# diy_stm.net
KiCad netlist of a schematic drawn in Altium Designer
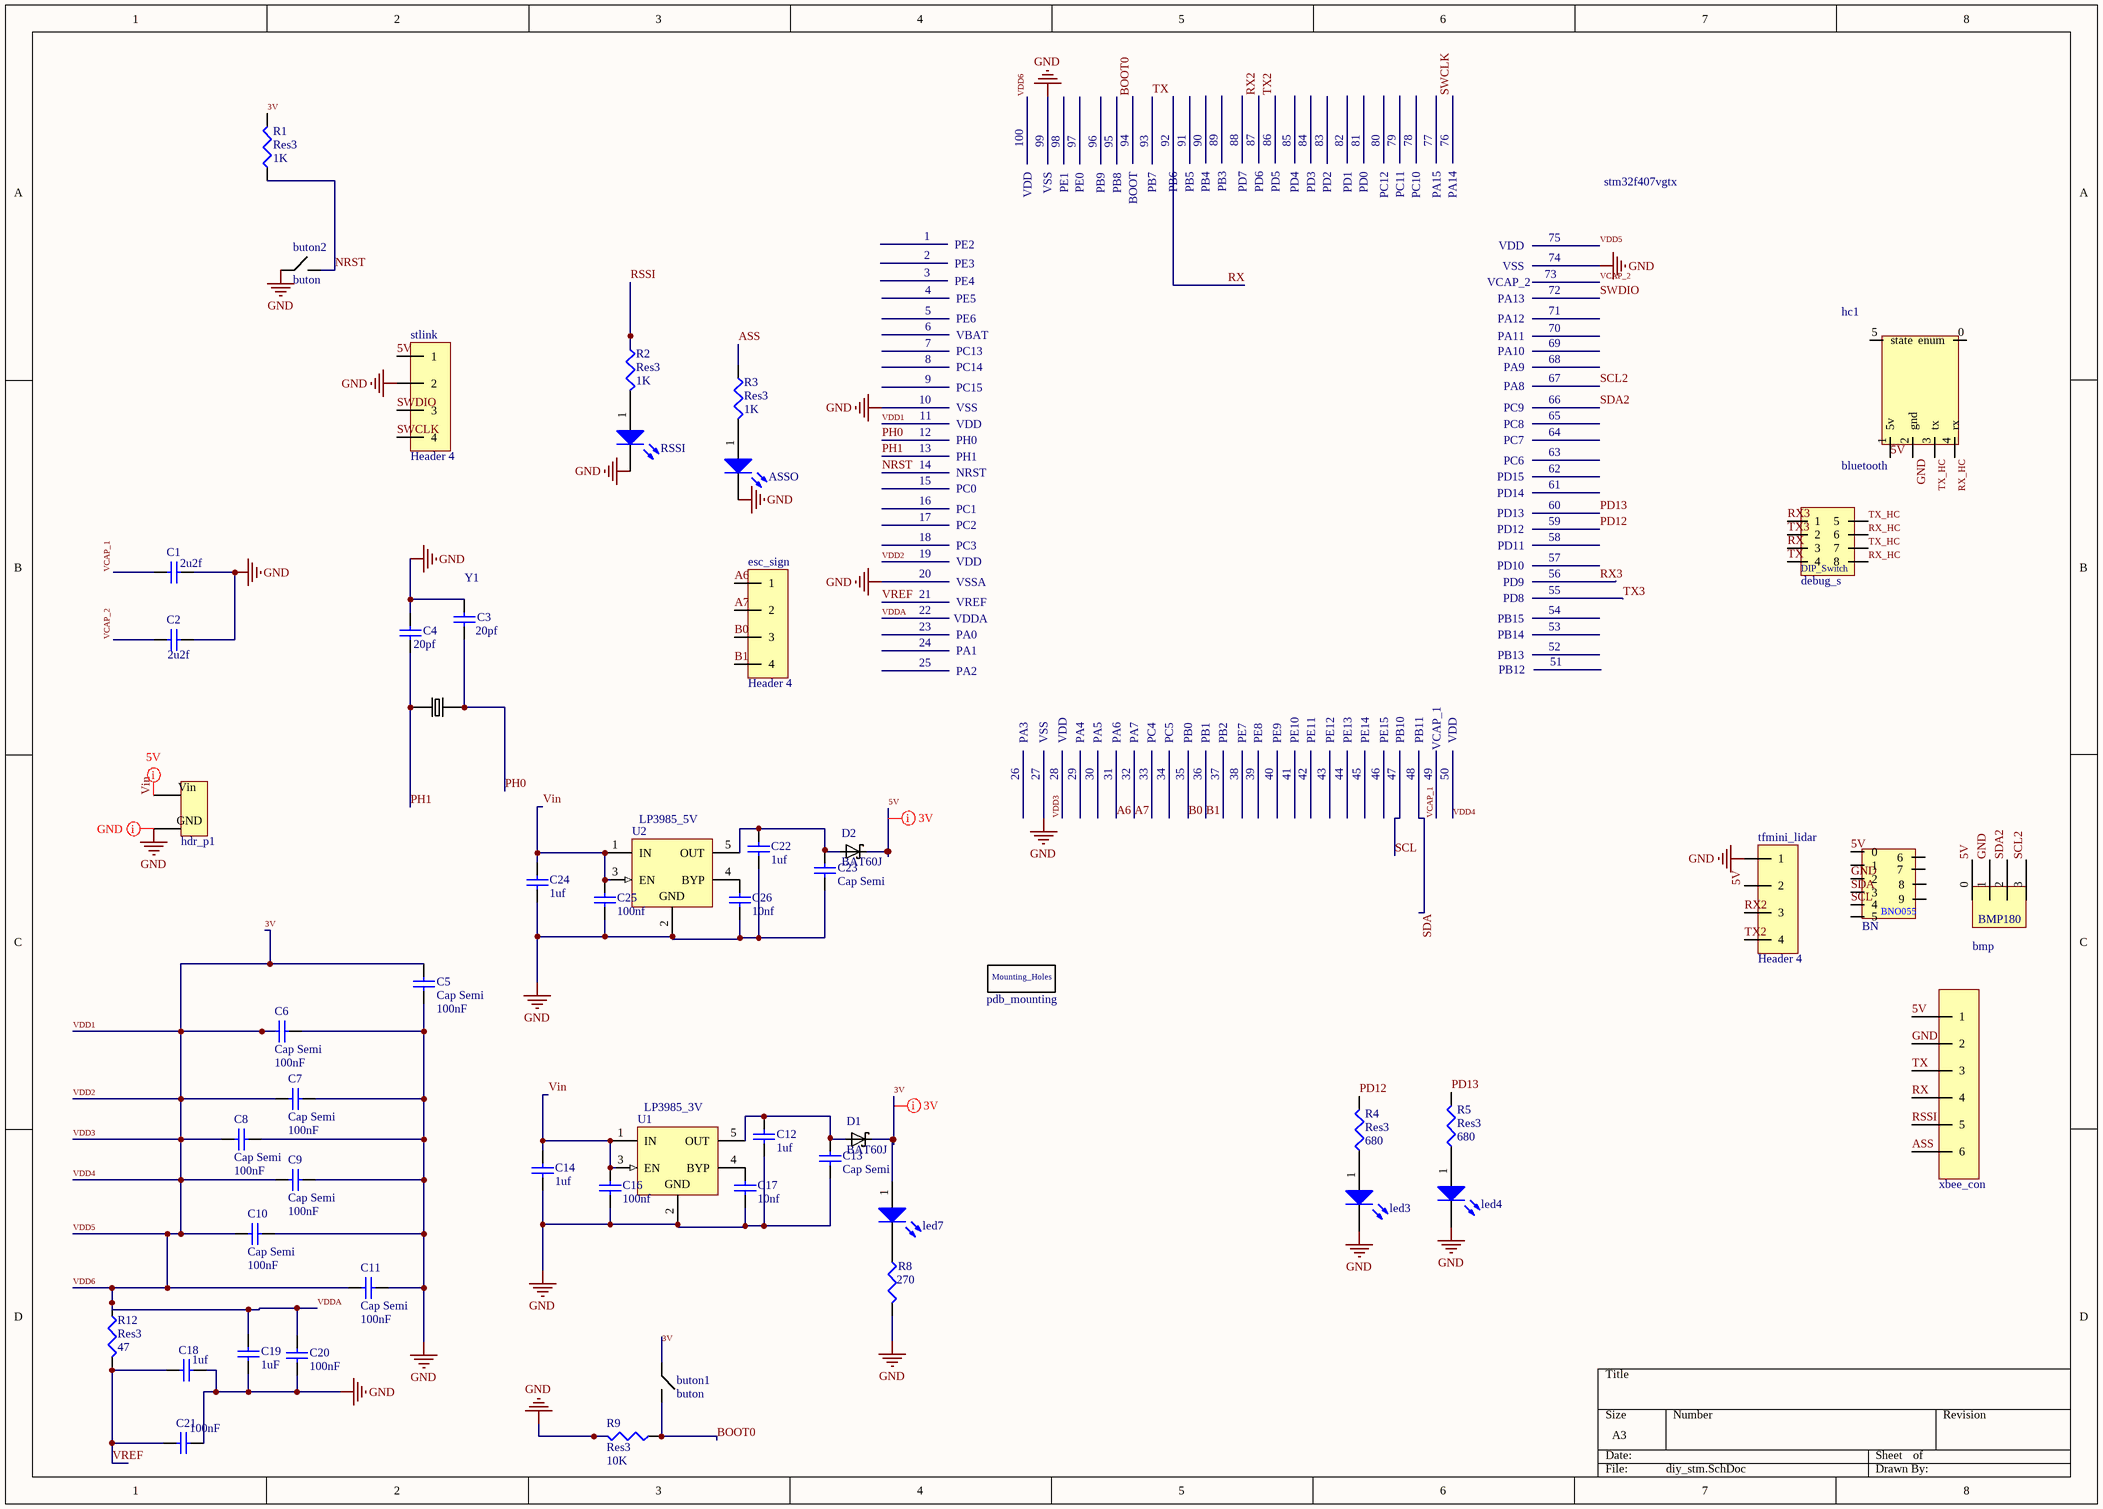
[diagram p0: diy_stm.SchDoc]

(export (version "E")
  (design (tool "Eeschema 10.0.6"))
  (components
    (comp (ref "ASSO")
      (value "L_green")
      (footprint "LED_0603")
      (libsource (lib "Led_edited") (part "L_green"))
    )
    (comp (ref "bmp") (value "bmp") (footprint "bmp") (libsource (lib "bmp180") (part "bmp")))
    (comp (ref "BN") (value "BNO055") (footprint "bno055") (libsource (lib "bno055") (part "BNO055")))
    (comp (ref "buton1") (value "buton") (footprint "buton") (libsource (lib "resistance") (part "buton")))
    (comp (ref "buton2") (value "buton") (footprint "buton") (libsource (lib "resistance") (part "buton")))
    (comp (ref "C1")
      (value "2u2f")
      (footprint "0603")
      (description "Capacitor (Semiconductor SIM Model)")
      (fields (field (name "Comment") "Cap Semi") (field (name "PUBLISHER") "Altium Limited"))
      (libsource (lib "Miscellaneous Devices") (part "Cap Semi"))
    )
    (comp (ref "C2")
      (value "2u2f")
      (footprint "0603")
      (description "Capacitor (Semiconductor SIM Model)")
      (fields (field (name "Comment") "Cap Semi") (field (name "PUBLISHER") "Altium Limited"))
      (libsource (lib "Miscellaneous Devices") (part "Cap Semi"))
    )
    (comp (ref "C3")
      (value "20pf")
      (footprint "0603")
      (description "Capacitor (Semiconductor SIM Model)")
      (fields (field (name "Comment") "Cap Semi") (field (name "PUBLISHER") "Altium Limited"))
      (libsource (lib "Miscellaneous Devices") (part "Cap Semi"))
    )
    (comp (ref "C4")
      (value "20pf")
      (footprint "0603")
      (description "Capacitor (Semiconductor SIM Model)")
      (fields (field (name "Comment") "Cap Semi") (field (name "PUBLISHER") "Altium Limited"))
      (libsource (lib "Miscellaneous Devices") (part "Cap Semi"))
    )
    (comp (ref "C5")
      (value "Cap Semi")
      (footprint "0603")
      (description "Capacitor (Semiconductor SIM Model)")
      (fields (field (name "ALTIUM_VALUE") "100nF") (field (name "PUBLISHER") "Altium Limited"))
      (libsource (lib "Miscellaneous Devices") (part "Cap Semi"))
    )
    (comp (ref "C6")
      (value "Cap Semi")
      (footprint "0603")
      (description "Capacitor (Semiconductor SIM Model)")
      (fields (field (name "ALTIUM_VALUE") "100nF") (field (name "PUBLISHER") "Altium Limited"))
      (libsource (lib "Miscellaneous Devices") (part "Cap Semi"))
    )
    (comp (ref "C7")
      (value "Cap Semi")
      (footprint "0603")
      (description "Capacitor (Semiconductor SIM Model)")
      (fields (field (name "ALTIUM_VALUE") "100nF") (field (name "PUBLISHER") "Altium Limited"))
      (libsource (lib "Miscellaneous Devices") (part "Cap Semi"))
    )
    (comp (ref "C8")
      (value "Cap Semi")
      (footprint "0603")
      (description "Capacitor (Semiconductor SIM Model)")
      (fields (field (name "ALTIUM_VALUE") "100nF") (field (name "PUBLISHER") "Altium Limited"))
      (libsource (lib "Miscellaneous Devices") (part "Cap Semi"))
    )
    (comp (ref "C9")
      (value "Cap Semi")
      (footprint "0603")
      (description "Capacitor (Semiconductor SIM Model)")
      (fields (field (name "ALTIUM_VALUE") "100nF") (field (name "PUBLISHER") "Altium Limited"))
      (libsource (lib "Miscellaneous Devices") (part "Cap Semi"))
    )
    (comp (ref "C10")
      (value "Cap Semi")
      (footprint "0603")
      (description "Capacitor (Semiconductor SIM Model)")
      (fields (field (name "ALTIUM_VALUE") "100nF") (field (name "PUBLISHER") "Altium Limited"))
      (libsource (lib "Miscellaneous Devices") (part "Cap Semi"))
    )
    (comp (ref "C11")
      (value "Cap Semi")
      (footprint "0603")
      (description "Capacitor (Semiconductor SIM Model)")
      (fields (field (name "ALTIUM_VALUE") "100nF") (field (name "PUBLISHER") "Altium Limited"))
      (libsource (lib "Miscellaneous Devices") (part "Cap Semi"))
    )
    (comp (ref "C12")
      (value "1uf")
      (footprint "0603")
      (description "Capacitor (Semiconductor SIM Model)")
      (fields (field (name "PUBLISHER") "Altium Limited"))
      (libsource (lib "Miscellaneous Devices") (part "Cap Semi"))
    )
    (comp (ref "C13")
      (value "Cap Semi")
      (footprint "0603")
      (description "Capacitor (Semiconductor SIM Model)")
      (fields (field (name "PUBLISHER") "Altium Limited"))
      (libsource (lib "Miscellaneous Devices") (part "Cap Semi"))
    )
    (comp (ref "C14")
      (value "1uf")
      (footprint "0603")
      (description "Capacitor (Semiconductor SIM Model)")
      (fields (field (name "PUBLISHER") "Altium Limited"))
      (libsource (lib "Miscellaneous Devices") (part "Cap Semi"))
    )
    (comp (ref "C16")
      (value "100nf")
      (footprint "0603")
      (description "Capacitor (Semiconductor SIM Model)")
      (fields (field (name "PUBLISHER") "Altium Limited"))
      (libsource (lib "Miscellaneous Devices") (part "Cap Semi"))
    )
    (comp (ref "C17")
      (value "10nf")
      (footprint "0603")
      (description "Capacitor (Semiconductor SIM Model)")
      (fields (field (name "PUBLISHER") "Altium Limited"))
      (libsource (lib "Miscellaneous Devices") (part "Cap Semi"))
    )
    (comp (ref "C18")
      (value "1uf")
      (footprint "0603")
      (description "Capacitor (Semiconductor SIM Model)")
      (fields (field (name "Comment") "Cap Semi") (field (name "PUBLISHER") "Altium Limited"))
      (libsource (lib "Miscellaneous Devices") (part "Cap Semi"))
    )
    (comp (ref "C19")
      (value "1uF")
      (footprint "0603")
      (description "Capacitor (Semiconductor SIM Model)")
      (fields (field (name "Comment") "Cap Semi") (field (name "PUBLISHER") "Altium Limited"))
      (libsource (lib "Miscellaneous Devices") (part "Cap Semi"))
    )
    (comp (ref "C20")
      (value "100nF")
      (footprint "0603")
      (description "Capacitor (Semiconductor SIM Model)")
      (fields (field (name "Comment") "Cap Semi") (field (name "PUBLISHER") "Altium Limited"))
      (libsource (lib "Miscellaneous Devices") (part "Cap Semi"))
    )
    (comp (ref "C21")
      (value "100nF")
      (footprint "0603")
      (description "Capacitor (Semiconductor SIM Model)")
      (fields (field (name "Comment") "Cap Semi") (field (name "PUBLISHER") "Altium Limited"))
      (libsource (lib "Miscellaneous Devices") (part "Cap Semi"))
    )
    (comp (ref "C22")
      (value "1uf")
      (footprint "0603")
      (description "Capacitor (Semiconductor SIM Model)")
      (fields (field (name "PUBLISHER") "Altium Limited"))
      (libsource (lib "Miscellaneous Devices") (part "Cap Semi"))
    )
    (comp (ref "C23")
      (value "Cap Semi")
      (footprint "0603")
      (description "Capacitor (Semiconductor SIM Model)")
      (fields (field (name "PUBLISHER") "Altium Limited"))
      (libsource (lib "Miscellaneous Devices") (part "Cap Semi"))
    )
    (comp (ref "C24")
      (value "1uf")
      (footprint "0603")
      (description "Capacitor (Semiconductor SIM Model)")
      (fields (field (name "PUBLISHER") "Altium Limited"))
      (libsource (lib "Miscellaneous Devices") (part "Cap Semi"))
    )
    (comp (ref "C25")
      (value "100nf")
      (footprint "0603")
      (description "Capacitor (Semiconductor SIM Model)")
      (fields (field (name "PUBLISHER") "Altium Limited"))
      (libsource (lib "Miscellaneous Devices") (part "Cap Semi"))
    )
    (comp (ref "C26")
      (value "10nf")
      (footprint "0603")
      (description "Capacitor (Semiconductor SIM Model)")
      (fields (field (name "PUBLISHER") "Altium Limited"))
      (libsource (lib "Miscellaneous Devices") (part "Cap Semi"))
    )
    (comp (ref "D1")
      (value "BAT60J")
      (footprint "*SOD323_ST_BAT60J(Primary)")
      (fields (field (name "MF") "STMicroelectronics"))
      (libsource (lib "BAT60J") (part "BAT60J"))
    )
    (comp (ref "D2")
      (value "BAT60J")
      (footprint "*SOD323_ST_BAT60J(Primary)")
      (fields (field (name "MF") "STMicroelectronics"))
      (libsource (lib "BAT60J") (part "BAT60J"))
    )
    (comp (ref "debug_s")
      (value "dipswitch")
      (footprint "jumer4_1.27")
      (libsource (lib "dipswitch") (part "dipswitch"))
    )
    (comp (ref "esc_sign")
      (value "Header 4")
      (footprint "hdr4_1.27")
      (libsource (lib "headers") (part "Header 4"))
    )
    (comp (ref "hc1")
      (value "bluetooth")
      (footprint "hc05")
      (description "bluetooth device hc 05")
      (libsource (lib "hc05") (part "hc05"))
    )
    (comp (ref "hdr_p1")
      (value "header_2_power")
      (footprint "HDR2_POWER")
      (libsource (lib "headers") (part "header_2_power"))
    )
    (comp (ref "led3")
      (value "L_green")
      (footprint "LED_0603")
      (libsource (lib "Led_edited") (part "L_green"))
    )
    (comp (ref "led4")
      (value "L_green")
      (footprint "LED_0603")
      (libsource (lib "Led_edited") (part "L_green"))
    )
    (comp (ref "led7")
      (value "L_green")
      (footprint "LED_0603")
      (libsource (lib "Led_edited") (part "L_green"))
    )
    (comp (ref "pdb_mounting")
      (value "pdb_mounting")
      (footprint "pdb_mounting_v1")
      (libsource (lib "mounting_holes") (part "pdb_mounting"))
    )
    (comp (ref "R1")
      (value "Res3")
      (footprint "J1-0603")
      (description "Resistor")
      (fields (field (name "ALTIUM_VALUE") "1K") (field (name "PUBLISHER") "Altium Limited"))
      (libsource (lib "Miscellaneous Devices") (part "Res3"))
    )
    (comp (ref "R2")
      (value "Res3")
      (footprint "J1-0603")
      (description "Resistor")
      (fields (field (name "ALTIUM_VALUE") "1K") (field (name "PUBLISHER") "Altium Limited"))
      (libsource (lib "Miscellaneous Devices") (part "Res3"))
    )
    (comp (ref "R3")
      (value "Res3")
      (footprint "J1-0603")
      (description "Resistor")
      (fields (field (name "ALTIUM_VALUE") "1K") (field (name "PUBLISHER") "Altium Limited"))
      (libsource (lib "Miscellaneous Devices") (part "Res3"))
    )
    (comp (ref "R4")
      (value "Res3")
      (footprint "J1-0603")
      (description "Resistor")
      (fields (field (name "ALTIUM_VALUE") "680") (field (name "PUBLISHER") "Altium Limited"))
      (libsource (lib "Miscellaneous Devices") (part "Res3"))
    )
    (comp (ref "R5")
      (value "Res3")
      (footprint "J1-0603")
      (description "Resistor")
      (fields (field (name "ALTIUM_VALUE") "680") (field (name "PUBLISHER") "Altium Limited"))
      (libsource (lib "Miscellaneous Devices") (part "Res3"))
    )
    (comp (ref "R8")
      (value "270")
      (footprint "J1-0603")
      (description "Resistor")
      (fields (field (name "Comment") "Res3") (field (name "PUBLISHER") "Altium Limited"))
      (libsource (lib "Miscellaneous Devices") (part "Res3"))
    )
    (comp (ref "R9")
      (value "Res3")
      (footprint "J1-0603")
      (description "Resistor")
      (fields (field (name "ALTIUM_VALUE") "10K") (field (name "PUBLISHER") "Altium Limited"))
      (libsource (lib "Miscellaneous Devices") (part "Res3"))
    )
    (comp (ref "R12")
      (value "Res3")
      (footprint "J1-0603")
      (description "Resistor")
      (fields (field (name "ALTIUM_VALUE") "47") (field (name "PUBLISHER") "Altium Limited"))
      (libsource (lib "Miscellaneous Devices") (part "Res3"))
    )
    (comp (ref "RSSI")
      (value "L_green")
      (footprint "LED_0603")
      (libsource (lib "Led_edited") (part "L_green"))
    )
    (comp (ref "stlink")
      (value "Header 4")
      (footprint "hdr4_1.27")
      (libsource (lib "headers") (part "Header 4"))
    )
    (comp (ref "stm32f407vgtx")
      (value "stm")
      (footprint "*QFP50P1600X1600X160-100N")
      (libsource (lib "stm32f407vgtx") (part "stm32f407"))
    )
    (comp (ref "tfmini_lidar")
      (value "Header 4")
      (footprint "hdr4_1.27")
      (libsource (lib "headers") (part "Header 4"))
    )
    (comp (ref "U1")
      (value "LP3985_3V")
      (footprint "MF05A_M")
      (description "Micropower, 150mA Low-Noise Ultra Low-Dropout CMOS Voltage Regulator, 5-pin SOT-23")
      (fields
        (field (name "MANUFACTURER") "National Semiconductor")
        (field (name "PARTNUMBER") "LP3985IM5-2.9")
      )
      (libsource (lib "TI_National_Semiconductor_LP3985IM5_2_9") (part "LP3985IM5-2.9"))
    )
    (comp (ref "U2")
      (value "LP3985_5V")
      (footprint "MF05A_M")
      (description "Micropower, 150mA Low-Noise Ultra Low-Dropout CMOS Voltage Regulator, 5-pin SOT-23")
      (fields
        (field (name "MANUFACTURER") "National Semiconductor")
        (field (name "PARTNUMBER") "LP3985IM5-2.9")
      )
      (libsource (lib "TI_National_Semiconductor_LP3985IM5_2_9") (part "LP3985IM5-2.9"))
    )
    (comp (ref "xbee_con")
      (value "header_6")
      (footprint "hdr6_1.27")
      (libsource (lib "headers") (part "header_6"))
    )
    (comp (ref "Y1")
      (value "ECS-122.8-20-1X")
      (footprint "*XTAL_ECS-122.8-20-1X")
      (description "HC-49/U Microprocessor Crystals 12.288MHz 20pF")
      (fields (field (name "MF") "ECS Inc."))
      (libsource (lib "crystal") (part "ECS-122.8-20-1X"))
    )
  )
  (nets
    (net (code "1") (name "/3V") (class "Default")
      (node (ref "C10") (pin "1") (pinfunction "1_1") (pintype "passive"))
      (node (ref "C11") (pin "1") (pinfunction "1_1") (pintype "passive"))
      (node (ref "C19") (pin "2") (pinfunction "2_2") (pintype "passive"))
      (node (ref "C20") (pin "2") (pinfunction "2_2") (pintype "passive"))
      (node (ref "C5") (pin "1") (pinfunction "1_1") (pintype "passive"))
      (node (ref "C6") (pin "1") (pinfunction "1_1") (pintype "passive"))
      (node (ref "C7") (pin "1") (pinfunction "1_1") (pintype "passive"))
      (node (ref "C8") (pin "1") (pinfunction "1_1") (pintype "passive"))
      (node (ref "C9") (pin "1") (pinfunction "1_1") (pintype "passive"))
      (node (ref "D1") (pin "C") (pinfunction "C_C") (pintype "passive"))
      (node (ref "R1") (pin "2") (pinfunction "2_2") (pintype "passive"))
      (node (ref "R12") (pin "1") (pinfunction "1_1") (pintype "passive"))
      (node (ref "buton1") (pin "1") (pinfunction "1_1") (pintype "passive"))
      (node (ref "led7") (pin "1") (pinfunction "V_1") (pintype "passive"))
      (node (ref "stm32f407vgtx") (pin "100") (pinfunction "VDD_100") (pintype "passive"))
      (node (ref "stm32f407vgtx") (pin "11") (pinfunction "VDD_11") (pintype "passive"))
      (node (ref "stm32f407vgtx") (pin "19") (pinfunction "VDD_19") (pintype "passive"))
      (node (ref "stm32f407vgtx") (pin "22") (pinfunction "VDDA_22") (pintype "passive"))
      (node (ref "stm32f407vgtx") (pin "28") (pinfunction "VDD_28") (pintype "passive"))
      (node (ref "stm32f407vgtx") (pin "50") (pinfunction "VDD_50") (pintype "passive"))
      (node (ref "stm32f407vgtx") (pin "75") (pinfunction "VDD_75") (pintype "passive"))
    )
    (net (code "2") (name "/5V") (class "Default")
      (node (ref "BN") (pin "0") (pinfunction "0_0") (pintype "passive"))
      (node (ref "D2") (pin "C") (pinfunction "C_C") (pintype "passive"))
      (node (ref "bmp") (pin "0") (pinfunction "0_0") (pintype "passive"))
      (node (ref "hc1") (pin "1") (pinfunction "5v_1") (pintype "passive"))
      (node (ref "stlink") (pin "1") (pinfunction "1_1") (pintype "passive"))
      (node (ref "tfmini_lidar") (pin "2") (pinfunction "2_2") (pintype "passive"))
      (node (ref "xbee_con") (pin "1") (pinfunction "1_1") (pintype "passive"))
    )
    (net (code "3") (name "/A6") (class "Default")
      (node (ref "esc_sign") (pin "1") (pinfunction "1_1") (pintype "passive"))
      (node (ref "stm32f407vgtx") (pin "31") (pinfunction "PA6_31") (pintype "passive"))
    )
    (net (code "4") (name "/A7") (class "Default")
      (node (ref "esc_sign") (pin "2") (pinfunction "2_2") (pintype "passive"))
      (node (ref "stm32f407vgtx") (pin "32") (pinfunction "PA7_32") (pintype "passive"))
    )
    (net (code "5") (name "/ASS") (class "Default")
      (node (ref "R3") (pin "1") (pinfunction "1_1") (pintype "passive"))
      (node (ref "xbee_con") (pin "6") (pinfunction "6_6") (pintype "passive"))
    )
    (net (code "6") (name "/B0") (class "Default")
      (node (ref "esc_sign") (pin "3") (pinfunction "3_3") (pintype "passive"))
      (node (ref "stm32f407vgtx") (pin "35") (pinfunction "PB0_35") (pintype "passive"))
    )
    (net (code "7") (name "/B1") (class "Default")
      (node (ref "esc_sign") (pin "4") (pinfunction "4_4") (pintype "passive"))
      (node (ref "stm32f407vgtx") (pin "36") (pinfunction "PB1_36") (pintype "passive"))
    )
    (net (code "8") (name "/BOOT0") (class "Default")
      (node (ref "R9") (pin "1") (pinfunction "1_1") (pintype "passive"))
      (node (ref "buton1") (pin "2") (pinfunction "2_2") (pintype "passive"))
      (node (ref "stm32f407vgtx") (pin "94") (pinfunction "BOOT_94") (pintype "passive"))
    )
    (net (code "9") (name "/NRST") (class "Default")
      (node (ref "R1") (pin "1") (pinfunction "1_1") (pintype "passive"))
      (node (ref "buton2") (pin "2") (pinfunction "2_2") (pintype "passive"))
      (node (ref "stm32f407vgtx") (pin "14") (pinfunction "NRST_14") (pintype "passive"))
    )
    (net (code "10") (name "/PD12") (class "Default")
      (node (ref "R4") (pin "2") (pinfunction "2_2") (pintype "passive"))
      (node (ref "stm32f407vgtx") (pin "59") (pinfunction "PD12_59") (pintype "passive"))
    )
    (net (code "11") (name "/PD13") (class "Default")
      (node (ref "R5") (pin "2") (pinfunction "2_2") (pintype "passive"))
      (node (ref "stm32f407vgtx") (pin "60") (pinfunction "PD13_60") (pintype "passive"))
    )
    (net (code "12") (name "/PH0") (class "Default")
      (node (ref "C3") (pin "2") (pinfunction "2_2") (pintype "passive"))
      (node (ref "Y1") (pin "1") (pinfunction "1_1") (pintype "passive"))
      (node (ref "stm32f407vgtx") (pin "12") (pinfunction "PH0_12") (pintype "passive"))
    )
    (net (code "13") (name "/PH1") (class "Default")
      (node (ref "C4") (pin "2") (pinfunction "2_2") (pintype "passive"))
      (node (ref "Y1") (pin "2") (pinfunction "2_2") (pintype "passive"))
      (node (ref "stm32f407vgtx") (pin "13") (pinfunction "PH1_13") (pintype "passive"))
    )
    (net (code "14") (name "/RSSI") (class "Default")
      (node (ref "R2") (pin "1") (pinfunction "1_1") (pintype "passive"))
      (node (ref "xbee_con") (pin "5") (pinfunction "5_5") (pintype "passive"))
    )
    (net (code "15") (name "/RX") (class "Default")
      (node (ref "debug_s") (pin "3") (pinfunction "3_3") (pintype "passive"))
      (node (ref "stm32f407vgtx") (pin "92") (pinfunction "PB6_92") (pintype "passive"))
      (node (ref "xbee_con") (pin "4") (pinfunction "4_4") (pintype "passive"))
    )
    (net (code "16") (name "/RX2") (class "Default")
      (node (ref "stm32f407vgtx") (pin "87") (pinfunction "PD6_87") (pintype "passive"))
      (node (ref "tfmini_lidar") (pin "3") (pinfunction "3_3") (pintype "passive"))
    )
    (net (code "17") (name "/RX3") (class "Default")
      (node (ref "debug_s") (pin "1") (pinfunction "1_1") (pintype "passive"))
      (node (ref "stm32f407vgtx") (pin "56") (pinfunction "PD9_56") (pintype "passive"))
    )
    (net (code "18") (name "/RX_HC") (class "Default")
      (node (ref "debug_s") (pin "6") (pinfunction "6_6") (pintype "passive"))
      (node (ref "debug_s") (pin "8") (pinfunction "8_8") (pintype "passive"))
      (node (ref "hc1") (pin "4") (pinfunction "rx_4") (pintype "passive"))
    )
    (net (code "19") (name "/SCL") (class "Default")
      (node (ref "BN") (pin "4") (pinfunction "4_4") (pintype "passive"))
      (node (ref "stm32f407vgtx") (pin "47") (pinfunction "PB10_47") (pintype "passive"))
    )
    (net (code "20") (name "/SCL2") (class "Default")
      (node (ref "bmp") (pin "3") (pinfunction "3_3") (pintype "passive"))
      (node (ref "stm32f407vgtx") (pin "67") (pinfunction "PA8_67") (pintype "passive"))
    )
    (net (code "21") (name "/SDA") (class "Default")
      (node (ref "BN") (pin "3") (pinfunction "3_3") (pintype "passive"))
      (node (ref "stm32f407vgtx") (pin "48") (pinfunction "PB11_48") (pintype "passive"))
    )
    (net (code "22") (name "/SDA2") (class "Default")
      (node (ref "bmp") (pin "2") (pinfunction "2_2") (pintype "passive"))
      (node (ref "stm32f407vgtx") (pin "66") (pinfunction "PC9_66") (pintype "passive"))
    )
    (net (code "23") (name "/SWCLK") (class "Default")
      (node (ref "stlink") (pin "4") (pinfunction "4_4") (pintype "passive"))
      (node (ref "stm32f407vgtx") (pin "76") (pinfunction "PA14_76") (pintype "passive"))
    )
    (net (code "24") (name "/SWDIO") (class "Default")
      (node (ref "stlink") (pin "3") (pinfunction "3_3") (pintype "passive"))
      (node (ref "stm32f407vgtx") (pin "72") (pinfunction "PA13_72") (pintype "passive"))
    )
    (net (code "25") (name "/TX") (class "Default")
      (node (ref "debug_s") (pin "4") (pinfunction "4_4") (pintype "passive"))
      (node (ref "stm32f407vgtx") (pin "93") (pinfunction "PB7_93") (pintype "passive"))
      (node (ref "xbee_con") (pin "3") (pinfunction "3_3") (pintype "passive"))
    )
    (net (code "26") (name "/TX2") (class "Default")
      (node (ref "stm32f407vgtx") (pin "86") (pinfunction "PD5_86") (pintype "passive"))
      (node (ref "tfmini_lidar") (pin "4") (pinfunction "4_4") (pintype "passive"))
    )
    (net (code "27") (name "/TX3") (class "Default")
      (node (ref "debug_s") (pin "2") (pinfunction "2_2") (pintype "passive"))
      (node (ref "stm32f407vgtx") (pin "55") (pinfunction "PD8_55") (pintype "passive"))
    )
    (net (code "28") (name "/TX_HC") (class "Default")
      (node (ref "debug_s") (pin "5") (pinfunction "5_5") (pintype "passive"))
      (node (ref "debug_s") (pin "7") (pinfunction "7_7") (pintype "passive"))
      (node (ref "hc1") (pin "3") (pinfunction "tx_3") (pintype "passive"))
    )
    (net (code "29") (name "/VCAP_1") (class "Default")
      (node (ref "C1") (pin "2") (pinfunction "2_2") (pintype "passive"))
      (node (ref "stm32f407vgtx") (pin "49") (pinfunction "VCAP_1_49") (pintype "passive"))
    )
    (net (code "30") (name "/VCAP_2") (class "Default")
      (node (ref "C2") (pin "2") (pinfunction "2_2") (pintype "passive"))
      (node (ref "stm32f407vgtx") (pin "73") (pinfunction "VCAP_2_73") (pintype "passive"))
    )
    (net (code "31") (name "/VREF") (class "Default")
      (node (ref "C18") (pin "1") (pinfunction "1_1") (pintype "passive"))
      (node (ref "C21") (pin "1") (pinfunction "1_1") (pintype "passive"))
      (node (ref "R12") (pin "2") (pinfunction "2_2") (pintype "passive"))
      (node (ref "stm32f407vgtx") (pin "21") (pinfunction "VREF_21") (pintype "passive"))
    )
    (net (code "32") (name "/Vin") (class "Default")
      (node (ref "C14") (pin "2") (pinfunction "2_2") (pintype "passive"))
      (node (ref "C16") (pin "2") (pinfunction "2_2") (pintype "passive"))
      (node (ref "C24") (pin "2") (pinfunction "2_2") (pintype "passive"))
      (node (ref "C25") (pin "2") (pinfunction "2_2") (pintype "passive"))
      (node (ref "U1") (pin "1") (pinfunction "IN_1") (pintype "power_in"))
      (node (ref "U1") (pin "3") (pinfunction "EN_3") (pintype "input"))
      (node (ref "U2") (pin "1") (pinfunction "IN_1") (pintype "power_in"))
      (node (ref "U2") (pin "3") (pinfunction "EN_3") (pintype "input"))
      (node (ref "hdr_p1") (pin "Vin") (pinfunction "1_Vin") (pintype "passive"))
    )
    (net (code "33") (name "GND") (class "Default")
      (node (ref "ASSO") (pin "2") (pinfunction "K_2") (pintype "passive"))
      (node (ref "BN") (pin "2") (pinfunction "2_2") (pintype "passive"))
      (node (ref "C1") (pin "1") (pinfunction "1_1") (pintype "passive"))
      (node (ref "C10") (pin "2") (pinfunction "2_2") (pintype "passive"))
      (node (ref "C11") (pin "2") (pinfunction "2_2") (pintype "passive"))
      (node (ref "C12") (pin "1") (pinfunction "1_1") (pintype "passive"))
      (node (ref "C13") (pin "1") (pinfunction "1_1") (pintype "passive"))
      (node (ref "C14") (pin "1") (pinfunction "1_1") (pintype "passive"))
      (node (ref "C16") (pin "1") (pinfunction "1_1") (pintype "passive"))
      (node (ref "C17") (pin "1") (pinfunction "1_1") (pintype "passive"))
      (node (ref "C18") (pin "2") (pinfunction "2_2") (pintype "passive"))
      (node (ref "C19") (pin "1") (pinfunction "1_1") (pintype "passive"))
      (node (ref "C2") (pin "1") (pinfunction "1_1") (pintype "passive"))
      (node (ref "C20") (pin "1") (pinfunction "1_1") (pintype "passive"))
      (node (ref "C21") (pin "2") (pinfunction "2_2") (pintype "passive"))
      (node (ref "C22") (pin "1") (pinfunction "1_1") (pintype "passive"))
      (node (ref "C23") (pin "1") (pinfunction "1_1") (pintype "passive"))
      (node (ref "C24") (pin "1") (pinfunction "1_1") (pintype "passive"))
      (node (ref "C25") (pin "1") (pinfunction "1_1") (pintype "passive"))
      (node (ref "C26") (pin "1") (pinfunction "1_1") (pintype "passive"))
      (node (ref "C3") (pin "1") (pinfunction "1_1") (pintype "passive"))
      (node (ref "C4") (pin "1") (pinfunction "1_1") (pintype "passive"))
      (node (ref "C5") (pin "2") (pinfunction "2_2") (pintype "passive"))
      (node (ref "C6") (pin "2") (pinfunction "2_2") (pintype "passive"))
      (node (ref "C7") (pin "2") (pinfunction "2_2") (pintype "passive"))
      (node (ref "C8") (pin "2") (pinfunction "2_2") (pintype "passive"))
      (node (ref "C9") (pin "2") (pinfunction "2_2") (pintype "passive"))
      (node (ref "R8") (pin "2") (pinfunction "2_2") (pintype "passive"))
      (node (ref "R9") (pin "2") (pinfunction "2_2") (pintype "passive"))
      (node (ref "RSSI") (pin "2") (pinfunction "K_2") (pintype "passive"))
      (node (ref "U1") (pin "2") (pinfunction "GND_2") (pintype "power_in"))
      (node (ref "U2") (pin "2") (pinfunction "GND_2") (pintype "power_in"))
      (node (ref "bmp") (pin "1") (pinfunction "1_1") (pintype "passive"))
      (node (ref "buton2") (pin "1") (pinfunction "1_1") (pintype "passive"))
      (node (ref "hc1") (pin "2") (pinfunction "gnd_2") (pintype "passive"))
      (node (ref "hdr_p1") (pin "GND") (pinfunction "2_GND") (pintype "passive"))
      (node (ref "led3") (pin "2") (pinfunction "K_2") (pintype "passive"))
      (node (ref "led4") (pin "2") (pinfunction "K_2") (pintype "passive"))
      (node (ref "stlink") (pin "2") (pinfunction "2_2") (pintype "passive"))
      (node (ref "stm32f407vgtx") (pin "10") (pinfunction "VSS_10") (pintype "passive"))
      (node (ref "stm32f407vgtx") (pin "20") (pinfunction "VSSA_20") (pintype "passive"))
      (node (ref "stm32f407vgtx") (pin "27") (pinfunction "VSS_27") (pintype "passive"))
      (node (ref "stm32f407vgtx") (pin "74") (pinfunction "VSS_74") (pintype "passive"))
      (node (ref "stm32f407vgtx") (pin "99") (pinfunction "VSS_99") (pintype "passive"))
      (node (ref "tfmini_lidar") (pin "1") (pinfunction "1_1") (pintype "passive"))
      (node (ref "xbee_con") (pin "2") (pinfunction "2_2") (pintype "passive"))
    )
    (net (code "34") (name "Net-(ASSO-V)") (class "Default")
      (node (ref "ASSO") (pin "1") (pinfunction "V_1") (pintype "passive"))
      (node (ref "R3") (pin "2") (pinfunction "2_2") (pintype "passive"))
    )
    (net (code "35") (name "Net-(RSSI-V)") (class "Default")
      (node (ref "R2") (pin "2") (pinfunction "2_2") (pintype "passive"))
      (node (ref "RSSI") (pin "1") (pinfunction "V_1") (pintype "passive"))
    )
    (net (code "36") (name "Net-(U1-BYP)") (class "Default")
      (node (ref "C17") (pin "2") (pinfunction "2_2") (pintype "passive"))
      (node (ref "U1") (pin "4") (pinfunction "BYP_4") (pintype "passive"))
    )
    (net (code "37") (name "Net-(U1-OUT)") (class "Default")
      (node (ref "C12") (pin "2") (pinfunction "2_2") (pintype "passive"))
      (node (ref "C13") (pin "2") (pinfunction "2_2") (pintype "passive"))
      (node (ref "D1") (pin "A") (pinfunction "A_A") (pintype "passive"))
      (node (ref "U1") (pin "5") (pinfunction "OUT_5") (pintype "power_in"))
    )
    (net (code "38") (name "Net-(U2-BYP)") (class "Default")
      (node (ref "C26") (pin "2") (pinfunction "2_2") (pintype "passive"))
      (node (ref "U2") (pin "4") (pinfunction "BYP_4") (pintype "passive"))
    )
    (net (code "39") (name "Net-(U2-OUT)") (class "Default")
      (node (ref "C22") (pin "2") (pinfunction "2_2") (pintype "passive"))
      (node (ref "C23") (pin "2") (pinfunction "2_2") (pintype "passive"))
      (node (ref "D2") (pin "A") (pinfunction "A_A") (pintype "passive"))
      (node (ref "U2") (pin "5") (pinfunction "OUT_5") (pintype "power_in"))
    )
    (net (code "40") (name "Net-(led3-V)") (class "Default")
      (node (ref "R4") (pin "1") (pinfunction "1_1") (pintype "passive"))
      (node (ref "led3") (pin "1") (pinfunction "V_1") (pintype "passive"))
    )
    (net (code "41") (name "Net-(led4-V)") (class "Default")
      (node (ref "R5") (pin "1") (pinfunction "1_1") (pintype "passive"))
      (node (ref "led4") (pin "1") (pinfunction "V_1") (pintype "passive"))
    )
    (net (code "42") (name "Net-(led7-K)") (class "Default")
      (node (ref "R8") (pin "1") (pinfunction "1_1") (pintype "passive"))
      (node (ref "led7") (pin "2") (pinfunction "K_2") (pintype "passive"))
    )
    (net (code "43") (name "unconnected-(BN-Pad1)") (class "Default")
      (node (ref "BN") (pin "1") (pinfunction "1_1") (pintype "passive"))
    )
    (net (code "44") (name "unconnected-(BN-Pad5)") (class "Default")
      (node (ref "BN") (pin "5") (pinfunction "5_5") (pintype "passive"))
    )
    (net (code "45") (name "unconnected-(BN-Pad6)") (class "Default")
      (node (ref "BN") (pin "6") (pinfunction "6_6") (pintype "passive"))
    )
    (net (code "46") (name "unconnected-(BN-Pad7)") (class "Default")
      (node (ref "BN") (pin "7") (pinfunction "7_7") (pintype "passive"))
    )
    (net (code "47") (name "unconnected-(BN-Pad8)") (class "Default")
      (node (ref "BN") (pin "8") (pinfunction "8_8") (pintype "passive"))
    )
    (net (code "48") (name "unconnected-(BN-Pad9)") (class "Default")
      (node (ref "BN") (pin "9") (pinfunction "9_9") (pintype "passive"))
    )
    (net (code "49") (name "unconnected-(hc1-enum-Pad0)") (class "Default")
      (node (ref "hc1") (pin "0") (pinfunction "enum_0") (pintype "passive"))
    )
    (net (code "50") (name "unconnected-(hc1-state-Pad5)") (class "Default")
      (node (ref "hc1") (pin "5") (pinfunction "state_5") (pintype "passive"))
    )
    (net (code "51") (name "unconnected-(stm32f407vgtx-PA0-Pad23)") (class "Default")
      (node (ref "stm32f407vgtx") (pin "23") (pinfunction "PA0_23") (pintype "passive"))
    )
    (net (code "52") (name "unconnected-(stm32f407vgtx-PA1-Pad24)") (class "Default")
      (node (ref "stm32f407vgtx") (pin "24") (pinfunction "PA1_24") (pintype "passive"))
    )
    (net (code "53") (name "unconnected-(stm32f407vgtx-PA2-Pad25)") (class "Default")
      (node (ref "stm32f407vgtx") (pin "25") (pinfunction "PA2_25") (pintype "passive"))
    )
    (net (code "54") (name "unconnected-(stm32f407vgtx-PA3-Pad26)") (class "Default")
      (node (ref "stm32f407vgtx") (pin "26") (pinfunction "PA3_26") (pintype "passive"))
    )
    (net (code "55") (name "unconnected-(stm32f407vgtx-PA4-Pad29)") (class "Default")
      (node (ref "stm32f407vgtx") (pin "29") (pinfunction "PA4_29") (pintype "passive"))
    )
    (net (code "56") (name "unconnected-(stm32f407vgtx-PA5-Pad30)") (class "Default")
      (node (ref "stm32f407vgtx") (pin "30") (pinfunction "PA5_30") (pintype "passive"))
    )
    (net (code "57") (name "unconnected-(stm32f407vgtx-PA9-Pad68)") (class "Default")
      (node (ref "stm32f407vgtx") (pin "68") (pinfunction "PA9_68") (pintype "passive"))
    )
    (net (code "58") (name "unconnected-(stm32f407vgtx-PA10-Pad69)") (class "Default")
      (node (ref "stm32f407vgtx") (pin "69") (pinfunction "PA10_69") (pintype "passive"))
    )
    (net (code "59") (name "unconnected-(stm32f407vgtx-PA11-Pad70)") (class "Default")
      (node (ref "stm32f407vgtx") (pin "70") (pinfunction "PA11_70") (pintype "passive"))
    )
    (net (code "60") (name "unconnected-(stm32f407vgtx-PA12-Pad71)") (class "Default")
      (node (ref "stm32f407vgtx") (pin "71") (pinfunction "PA12_71") (pintype "passive"))
    )
    (net (code "61") (name "unconnected-(stm32f407vgtx-PA15-Pad77)") (class "Default")
      (node (ref "stm32f407vgtx") (pin "77") (pinfunction "PA15_77") (pintype "passive"))
    )
    (net (code "62") (name "unconnected-(stm32f407vgtx-PB2-Pad37)") (class "Default")
      (node (ref "stm32f407vgtx") (pin "37") (pinfunction "PB2_37") (pintype "passive"))
    )
    (net (code "63") (name "unconnected-(stm32f407vgtx-PB3-Pad89)") (class "Default")
      (node (ref "stm32f407vgtx") (pin "89") (pinfunction "PB3_89") (pintype "passive"))
    )
    (net (code "64") (name "unconnected-(stm32f407vgtx-PB4-Pad90)") (class "Default")
      (node (ref "stm32f407vgtx") (pin "90") (pinfunction "PB4_90") (pintype "passive"))
    )
    (net (code "65") (name "unconnected-(stm32f407vgtx-PB5-Pad91)") (class "Default")
      (node (ref "stm32f407vgtx") (pin "91") (pinfunction "PB5_91") (pintype "passive"))
    )
    (net (code "66") (name "unconnected-(stm32f407vgtx-PB8-Pad95)") (class "Default")
      (node (ref "stm32f407vgtx") (pin "95") (pinfunction "PB8_95") (pintype "passive"))
    )
    (net (code "67") (name "unconnected-(stm32f407vgtx-PB9-Pad96)") (class "Default")
      (node (ref "stm32f407vgtx") (pin "96") (pinfunction "PB9_96") (pintype "passive"))
    )
    (net (code "68") (name "unconnected-(stm32f407vgtx-PB12-Pad51)") (class "Default")
      (node (ref "stm32f407vgtx") (pin "51") (pinfunction "PB12_51") (pintype "passive"))
    )
    (net (code "69") (name "unconnected-(stm32f407vgtx-PB13-Pad52)") (class "Default")
      (node (ref "stm32f407vgtx") (pin "52") (pinfunction "PB13_52") (pintype "passive"))
    )
    (net (code "70") (name "unconnected-(stm32f407vgtx-PB14-Pad53)") (class "Default")
      (node (ref "stm32f407vgtx") (pin "53") (pinfunction "PB14_53") (pintype "passive"))
    )
    (net (code "71") (name "unconnected-(stm32f407vgtx-PB15-Pad54)") (class "Default")
      (node (ref "stm32f407vgtx") (pin "54") (pinfunction "PB15_54") (pintype "passive"))
    )
    (net (code "72") (name "unconnected-(stm32f407vgtx-PC0-Pad15)") (class "Default")
      (node (ref "stm32f407vgtx") (pin "15") (pinfunction "PC0_15") (pintype "passive"))
    )
    (net (code "73") (name "unconnected-(stm32f407vgtx-PC1-Pad16)") (class "Default")
      (node (ref "stm32f407vgtx") (pin "16") (pinfunction "PC1_16") (pintype "passive"))
    )
    (net (code "74") (name "unconnected-(stm32f407vgtx-PC2-Pad17)") (class "Default")
      (node (ref "stm32f407vgtx") (pin "17") (pinfunction "PC2_17") (pintype "passive"))
    )
    (net (code "75") (name "unconnected-(stm32f407vgtx-PC3-Pad18)") (class "Default")
      (node (ref "stm32f407vgtx") (pin "18") (pinfunction "PC3_18") (pintype "passive"))
    )
    (net (code "76") (name "unconnected-(stm32f407vgtx-PC4-Pad33)") (class "Default")
      (node (ref "stm32f407vgtx") (pin "33") (pinfunction "PC4_33") (pintype "passive"))
    )
    (net (code "77") (name "unconnected-(stm32f407vgtx-PC5-Pad34)") (class "Default")
      (node (ref "stm32f407vgtx") (pin "34") (pinfunction "PC5_34") (pintype "passive"))
    )
    (net (code "78") (name "unconnected-(stm32f407vgtx-PC6-Pad63)") (class "Default")
      (node (ref "stm32f407vgtx") (pin "63") (pinfunction "PC6_63") (pintype "passive"))
    )
    (net (code "79") (name "unconnected-(stm32f407vgtx-PC7-Pad64)") (class "Default")
      (node (ref "stm32f407vgtx") (pin "64") (pinfunction "PC7_64") (pintype "passive"))
    )
    (net (code "80") (name "unconnected-(stm32f407vgtx-PC8-Pad65)") (class "Default")
      (node (ref "stm32f407vgtx") (pin "65") (pinfunction "PC8_65") (pintype "passive"))
    )
    (net (code "81") (name "unconnected-(stm32f407vgtx-PC10-Pad78)") (class "Default")
      (node (ref "stm32f407vgtx") (pin "78") (pinfunction "PC10_78") (pintype "passive"))
    )
    (net (code "82") (name "unconnected-(stm32f407vgtx-PC11-Pad79)") (class "Default")
      (node (ref "stm32f407vgtx") (pin "79") (pinfunction "PC11_79") (pintype "passive"))
    )
    (net (code "83") (name "unconnected-(stm32f407vgtx-PC12-Pad80)") (class "Default")
      (node (ref "stm32f407vgtx") (pin "80") (pinfunction "PC12_80") (pintype "passive"))
    )
    (net (code "84") (name "unconnected-(stm32f407vgtx-PC13-Pad7)") (class "Default")
      (node (ref "stm32f407vgtx") (pin "7") (pinfunction "PC13_7") (pintype "passive"))
    )
    (net (code "85") (name "unconnected-(stm32f407vgtx-PC14-Pad8)") (class "Default")
      (node (ref "stm32f407vgtx") (pin "8") (pinfunction "PC14_8") (pintype "passive"))
    )
    (net (code "86") (name "unconnected-(stm32f407vgtx-PC15-Pad9)") (class "Default")
      (node (ref "stm32f407vgtx") (pin "9") (pinfunction "PC15_9") (pintype "passive"))
    )
    (net (code "87") (name "unconnected-(stm32f407vgtx-PD0-Pad81)") (class "Default")
      (node (ref "stm32f407vgtx") (pin "81") (pinfunction "PD0_81") (pintype "passive"))
    )
    (net (code "88") (name "unconnected-(stm32f407vgtx-PD1-Pad82)") (class "Default")
      (node (ref "stm32f407vgtx") (pin "82") (pinfunction "PD1_82") (pintype "passive"))
    )
    (net (code "89") (name "unconnected-(stm32f407vgtx-PD2-Pad83)") (class "Default")
      (node (ref "stm32f407vgtx") (pin "83") (pinfunction "PD2_83") (pintype "passive"))
    )
    (net (code "90") (name "unconnected-(stm32f407vgtx-PD3-Pad84)") (class "Default")
      (node (ref "stm32f407vgtx") (pin "84") (pinfunction "PD3_84") (pintype "passive"))
    )
    (net (code "91") (name "unconnected-(stm32f407vgtx-PD4-Pad85)") (class "Default")
      (node (ref "stm32f407vgtx") (pin "85") (pinfunction "PD4_85") (pintype "passive"))
    )
    (net (code "92") (name "unconnected-(stm32f407vgtx-PD7-Pad88)") (class "Default")
      (node (ref "stm32f407vgtx") (pin "88") (pinfunction "PD7_88") (pintype "passive"))
    )
    (net (code "93") (name "unconnected-(stm32f407vgtx-PD10-Pad57)") (class "Default")
      (node (ref "stm32f407vgtx") (pin "57") (pinfunction "PD10_57") (pintype "passive"))
    )
    (net (code "94") (name "unconnected-(stm32f407vgtx-PD11-Pad58)") (class "Default")
      (node (ref "stm32f407vgtx") (pin "58") (pinfunction "PD11_58") (pintype "passive"))
    )
    (net (code "95") (name "unconnected-(stm32f407vgtx-PD14-Pad61)") (class "Default")
      (node (ref "stm32f407vgtx") (pin "61") (pinfunction "PD14_61") (pintype "passive"))
    )
    (net (code "96") (name "unconnected-(stm32f407vgtx-PD15-Pad62)") (class "Default")
      (node (ref "stm32f407vgtx") (pin "62") (pinfunction "PD15_62") (pintype "passive"))
    )
    (net (code "97") (name "unconnected-(stm32f407vgtx-PE0-Pad97)") (class "Default")
      (node (ref "stm32f407vgtx") (pin "97") (pinfunction "PE0_97") (pintype "passive"))
    )
    (net (code "98") (name "unconnected-(stm32f407vgtx-PE1-Pad98)") (class "Default")
      (node (ref "stm32f407vgtx") (pin "98") (pinfunction "PE1_98") (pintype "passive"))
    )
    (net (code "99") (name "unconnected-(stm32f407vgtx-PE2-Pad1)") (class "Default")
      (node (ref "stm32f407vgtx") (pin "1") (pinfunction "PE2_1") (pintype "passive"))
    )
    (net (code "100") (name "unconnected-(stm32f407vgtx-PE3-Pad2)") (class "Default")
      (node (ref "stm32f407vgtx") (pin "2") (pinfunction "PE3_2") (pintype "passive"))
    )
    (net (code "101") (name "unconnected-(stm32f407vgtx-PE4-Pad3)") (class "Default")
      (node (ref "stm32f407vgtx") (pin "3") (pinfunction "PE4_3") (pintype "passive"))
    )
    (net (code "102") (name "unconnected-(stm32f407vgtx-PE5-Pad4)") (class "Default")
      (node (ref "stm32f407vgtx") (pin "4") (pinfunction "PE5_4") (pintype "passive"))
    )
    (net (code "103") (name "unconnected-(stm32f407vgtx-PE6-Pad5)") (class "Default")
      (node (ref "stm32f407vgtx") (pin "5") (pinfunction "PE6_5") (pintype "passive"))
    )
    (net (code "104") (name "unconnected-(stm32f407vgtx-PE7-Pad38)") (class "Default")
      (node (ref "stm32f407vgtx") (pin "38") (pinfunction "PE7_38") (pintype "passive"))
    )
    (net (code "105") (name "unconnected-(stm32f407vgtx-PE8-Pad39)") (class "Default")
      (node (ref "stm32f407vgtx") (pin "39") (pinfunction "PE8_39") (pintype "passive"))
    )
    (net (code "106") (name "unconnected-(stm32f407vgtx-PE9-Pad40)") (class "Default")
      (node (ref "stm32f407vgtx") (pin "40") (pinfunction "PE9_40") (pintype "passive"))
    )
    (net (code "107") (name "unconnected-(stm32f407vgtx-PE10-Pad41)") (class "Default")
      (node (ref "stm32f407vgtx") (pin "41") (pinfunction "PE10_41") (pintype "passive"))
    )
    (net (code "108") (name "unconnected-(stm32f407vgtx-PE11-Pad42)") (class "Default")
      (node (ref "stm32f407vgtx") (pin "42") (pinfunction "PE11_42") (pintype "passive"))
    )
    (net (code "109") (name "unconnected-(stm32f407vgtx-PE12-Pad43)") (class "Default")
      (node (ref "stm32f407vgtx") (pin "43") (pinfunction "PE12_43") (pintype "passive"))
    )
    (net (code "110") (name "unconnected-(stm32f407vgtx-PE13-Pad44)") (class "Default")
      (node (ref "stm32f407vgtx") (pin "44") (pinfunction "PE13_44") (pintype "passive"))
    )
    (net (code "111") (name "unconnected-(stm32f407vgtx-PE14-Pad45)") (class "Default")
      (node (ref "stm32f407vgtx") (pin "45") (pinfunction "PE14_45") (pintype "passive"))
    )
    (net (code "112") (name "unconnected-(stm32f407vgtx-PE15-Pad46)") (class "Default")
      (node (ref "stm32f407vgtx") (pin "46") (pinfunction "PE15_46") (pintype "passive"))
    )
    (net (code "113") (name "unconnected-(stm32f407vgtx-VBAT-Pad6)") (class "Default")
      (node (ref "stm32f407vgtx") (pin "6") (pinfunction "VBAT_6") (pintype "passive"))
    )
  )
)
